# TouScruino-avr-ui1-v0.net
KiCad netlist of a schematic drawn in EAGLE
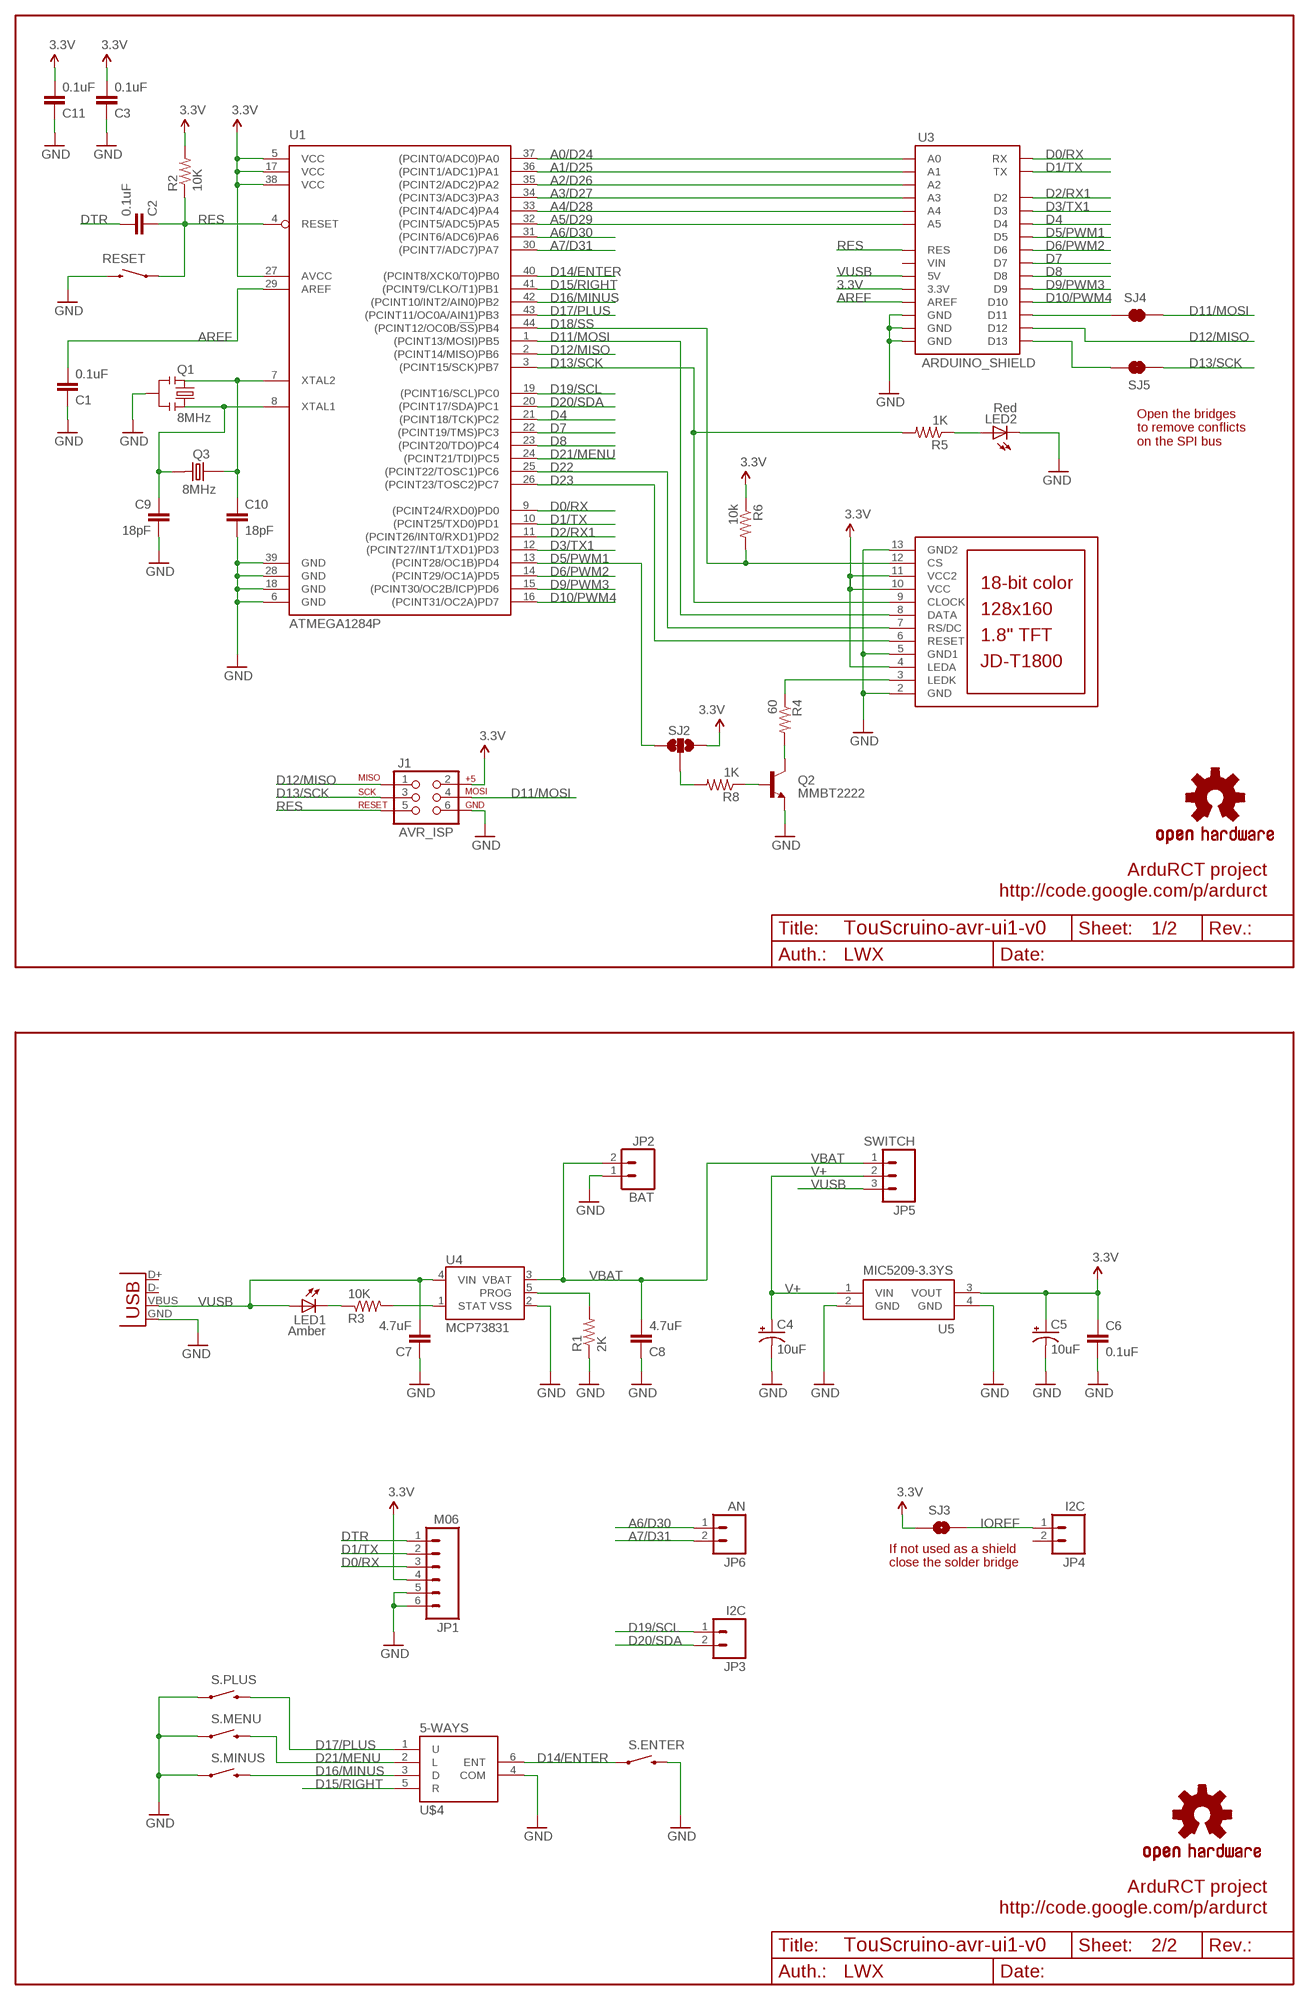
[diagram p0: schematic, sheet 1]

(export (version "E")
  (design (tool "Eeschema 10.0.6"))
  (components
    (comp (ref "C1")
      (value "0.1uF")
      (footprint "eagle-import:0805")
      (libsource (lib "eagle-import") (part "CAP0805"))
    )
    (comp (ref "C2")
      (value "0.1uF")
      (footprint "eagle-import:0805")
      (libsource (lib "eagle-import") (part "CAP0805"))
    )
    (comp (ref "C3")
      (value "0.1uF")
      (footprint "eagle-import:0805")
      (libsource (lib "eagle-import") (part "CAP0805"))
    )
    (comp (ref "C4")
      (value "10uF")
      (footprint "eagle-import:EIA3216")
      (libsource (lib "eagle-import") (part "CAP_POL1206"))
    )
    (comp (ref "C5")
      (value "10uF")
      (footprint "eagle-import:EIA3216")
      (libsource (lib "eagle-import") (part "CAP_POL1206"))
    )
    (comp (ref "C6")
      (value "0.1uF")
      (footprint "eagle-import:0805")
      (libsource (lib "eagle-import") (part "CAP0805"))
    )
    (comp (ref "C7")
      (value "4.7uF")
      (footprint "eagle-import:0805")
      (libsource (lib "eagle-import") (part "CAP0805"))
    )
    (comp (ref "C8")
      (value "4.7uF")
      (footprint "eagle-import:0805")
      (libsource (lib "eagle-import") (part "CAP0805"))
    )
    (comp (ref "C9")
      (value "18pF")
      (footprint "eagle-import:0603-CAP")
      (libsource (lib "eagle-import") (part "CAP0603-CAP"))
    )
    (comp (ref "C10")
      (value "18pF")
      (footprint "eagle-import:0603-CAP")
      (libsource (lib "eagle-import") (part "CAP0603-CAP"))
    )
    (comp (ref "C11")
      (value "0.1uF")
      (footprint "eagle-import:0805")
      (libsource (lib "eagle-import") (part "CAP0805"))
    )
    (comp (ref "J1")
      (value "AVR_ISP")
      (footprint "eagle-import:2X3")
      (libsource (lib "eagle-import") (part "AVR_SPI_PRG_6PTH"))
    )
    (comp (ref "JP1")
      (value "M06")
      (footprint "eagle-import:1X06")
      (libsource (lib "eagle-import") (part "M06"))
    )
    (comp (ref "JP2")
      (value "BAT")
      (footprint "eagle-import:JST-2-SMD")
      (libsource (lib "eagle-import") (part "M02-JST-2MM-SMT"))
    )
    (comp (ref "JP3")
      (value "I2C")
      (footprint "eagle-import:1X02")
      (libsource (lib "eagle-import") (part "M02"))
    )
    (comp (ref "JP4")
      (value "I2C")
      (footprint "eagle-import:1X02")
      (libsource (lib "eagle-import") (part "M02"))
    )
    (comp (ref "JP5")
      (value "SWITCH")
      (footprint "eagle-import:1X3_LONGPAD")
      (libsource (lib "eagle-import") (part "M03"))
    )
    (comp (ref "JP6")
      (value "AN")
      (footprint "eagle-import:1X02")
      (libsource (lib "eagle-import") (part "M02"))
    )
    (comp (ref "LCD1")
      (value "JD-T1800")
      (footprint "eagle-import:JD-T1800")
      (libsource (lib "eagle-import") (part "JD-T1800"))
    )
    (comp (ref "LED1")
      (value "Amber")
      (footprint "eagle-import:LED")
      (libsource (lib "eagle-import") (part "LED"))
    )
    (comp (ref "LED2")
      (value "Red")
      (footprint "eagle-import:LED")
      (libsource (lib "eagle-import") (part "LED"))
    )
    (comp (ref "Q1")
      (value "8MHz")
      (footprint "eagle-import:RESONATOR-SMD")
      (libsource (lib "eagle-import") (part "RESONATORSMD"))
    )
    (comp (ref "Q2")
      (value "MMBT2222")
      (footprint "eagle-import:SOT23-3")
      (libsource (lib "eagle-import") (part "TRANSISTOR_NPNSOT23-3"))
    )
    (comp (ref "Q3")
      (value "8MHz")
      (footprint "eagle-import:CRYSTAL_5X3.2")
      (libsource (lib "eagle-import") (part "CRYSTAL_5X3.2"))
    )
    (comp (ref "R1")
      (value "2K")
      (footprint "eagle-import:0805")
      (libsource (lib "eagle-import") (part "RESISTOR0805-RES"))
    )
    (comp (ref "R2")
      (value "10K")
      (footprint "eagle-import:0805")
      (libsource (lib "eagle-import") (part "RESISTOR0805-RES"))
    )
    (comp (ref "R3")
      (value "10K")
      (footprint "eagle-import:0805")
      (libsource (lib "eagle-import") (part "RESISTOR0805-RES"))
    )
    (comp (ref "R4")
      (value "60")
      (footprint "eagle-import:0805")
      (libsource (lib "eagle-import") (part "RESISTOR0805-RES"))
    )
    (comp (ref "R5")
      (value "1K")
      (footprint "eagle-import:0805")
      (libsource (lib "eagle-import") (part "RESISTOR0805-RES"))
    )
    (comp (ref "R6")
      (value "10k")
      (footprint "eagle-import:0805")
      (libsource (lib "eagle-import") (part "RESISTOR0805-RES"))
    )
    (comp (ref "R8")
      (value "1K")
      (footprint "eagle-import:0805")
      (libsource (lib "eagle-import") (part "RESISTOR0805-RES"))
    )
    (comp (ref "RESET")
      (value "SWITCH-MOMENTARY-2SMD")
      (footprint "eagle-import:TACTILE_SWITCH_SMD")
      (libsource (lib "eagle-import") (part "SWITCH-MOMENTARY-2SMD"))
    )
    (comp (ref "S.ENTER")
      (value "SWITCH_SMD")
      (footprint "eagle-import:TACTILE_SWITCH_SMD")
      (libsource (lib "eagle-import") (part "SWITCH_SMD"))
    )
    (comp (ref "S.MENU")
      (value "SWITCH_SMD")
      (footprint "eagle-import:TACTILE_SWITCH_SMD")
      (libsource (lib "eagle-import") (part "SWITCH_SMD"))
    )
    (comp (ref "S.MINUS")
      (value "SWITCH_SMD")
      (footprint "eagle-import:TACTILE_SWITCH_SMD")
      (libsource (lib "eagle-import") (part "SWITCH_SMD"))
    )
    (comp (ref "S.PLUS")
      (value "SWITCH_SMD")
      (footprint "eagle-import:TACTILE_SWITCH_SMD")
      (libsource (lib "eagle-import") (part "SWITCH_SMD"))
    )
    (comp (ref "SJ2")
      (value "SJ_2WAYS_1-2")
      (footprint "eagle-import:SJ_2WAYS_1-2_S")
      (libsource (lib "eagle-import") (part "SJ_2WAYS_1-2"))
    )
    (comp (ref "SJ3")
      (value "SOLDERJUMPERNO")
      (footprint "eagle-import:SJ_2S-NO")
      (libsource (lib "eagle-import") (part "SOLDERJUMPERNO"))
    )
    (comp (ref "SJ4")
      (value "SOLDERJUMPERTRACE")
      (footprint "eagle-import:SJ_2S-TRACE")
      (libsource (lib "eagle-import") (part "SOLDERJUMPERTRACE"))
    )
    (comp (ref "SJ5")
      (value "SOLDERJUMPERTRACE")
      (footprint "eagle-import:SJ_2S-TRACE")
      (libsource (lib "eagle-import") (part "SOLDERJUMPERTRACE"))
    )
    (comp (ref "U$3")
      (value "OSHW-LOGOM")
      (footprint "eagle-import:OSHW-LOGO-M")
      (libsource (lib "eagle-import") (part "OSHW-LOGOM"))
    )
    (comp (ref "U$4")
      (value "5-WAYS")
      (footprint "eagle-import:5-WAYS_ALPS")
      (libsource (lib "eagle-import") (part "5-WAYS"))
    )
    (comp (ref "U$5")
      (value "OSHW-LOGOM")
      (footprint "eagle-import:OSHW-LOGO-M")
      (libsource (lib "eagle-import") (part "OSHW-LOGOM"))
    )
    (comp (ref "U1")
      (value "ATMEGA1284P")
      (footprint "eagle-import:TQFP44")
      (libsource (lib "eagle-import") (part "ATMEGA324A"))
    )
    (comp (ref "U3")
      (value "ARDUINO_SHIELD")
      (footprint "eagle-import:ARDUINO_SHIELD")
      (libsource (lib "eagle-import") (part "ARDUINO_SHIELD"))
    )
    (comp (ref "U4")
      (value "MCP73831")
      (footprint "eagle-import:SOT23-5")
      (libsource (lib "eagle-import") (part "MCP73831"))
    )
    (comp (ref "U5")
      (value "MIC5209-3.3YS")
      (footprint "eagle-import:SOT223")
      (libsource (lib "eagle-import") (part "MIC5209"))
    )
    (comp (ref "X1")
      (value "USB")
      (footprint "eagle-import:USB-MICROB")
      (libsource (lib "eagle-import") (part "USB"))
    )
  )
  (nets
    (net (code "1") (name "/A0{slash}D24") (class "Default")
      (node (ref "U1") (pin "37") (pinfunction "(PCINT0/ADC0)PA0_37") (pintype "bidirectional"))
      (node (ref "U3") (pin "A0") (pinfunction "A0_A0") (pintype "bidirectional"))
    )
    (net (code "2") (name "/A1{slash}D25") (class "Default")
      (node (ref "U1") (pin "36") (pinfunction "(PCINT1/ADC1)PA1_36") (pintype "bidirectional"))
      (node (ref "U3") (pin "A1") (pinfunction "A1_A1") (pintype "bidirectional"))
    )
    (net (code "3") (name "/A2{slash}D26") (class "Default")
      (node (ref "U1") (pin "35") (pinfunction "(PCINT2/ADC2)PA2_35") (pintype "bidirectional"))
      (node (ref "U3") (pin "A2") (pinfunction "A2_A2") (pintype "bidirectional"))
    )
    (net (code "4") (name "/A3{slash}D27") (class "Default")
      (node (ref "U1") (pin "34") (pinfunction "(PCINT3/ADC3)PA3_34") (pintype "bidirectional"))
      (node (ref "U3") (pin "A3") (pinfunction "A3_A3") (pintype "bidirectional"))
    )
    (net (code "5") (name "/A4{slash}D28") (class "Default")
      (node (ref "U1") (pin "33") (pinfunction "(PCINT4/ADC4)PA4_33") (pintype "bidirectional"))
      (node (ref "U3") (pin "A4") (pinfunction "A4_A4") (pintype "bidirectional"))
    )
    (net (code "6") (name "/A5{slash}D29") (class "Default")
      (node (ref "U1") (pin "32") (pinfunction "(PCINT5/ADC5)PA5_32") (pintype "bidirectional"))
      (node (ref "U3") (pin "A5") (pinfunction "A5_A5") (pintype "bidirectional"))
    )
    (net (code "7") (name "/A6{slash}D30") (class "Default")
      (node (ref "JP6") (pin "1") (pinfunction "1_1") (pintype "passive"))
      (node (ref "U1") (pin "31") (pinfunction "(PCINT6/ADC6)PA6_31") (pintype "bidirectional"))
    )
    (net (code "8") (name "/A7{slash}D31") (class "Default")
      (node (ref "JP6") (pin "2") (pinfunction "2_2") (pintype "passive"))
      (node (ref "U1") (pin "30") (pinfunction "(PCINT7/ADC7)PA7_30") (pintype "bidirectional"))
    )
    (net (code "9") (name "/AREF") (class "Default")
      (node (ref "C1") (pin "2") (pinfunction "2_2") (pintype "passive"))
      (node (ref "U1") (pin "29") (pinfunction "AREF_29") (pintype "passive"))
      (node (ref "U3") (pin "AREF") (pinfunction "AREF_AREF") (pintype "bidirectional"))
    )
    (net (code "10") (name "/D0{slash}RX") (class "Default")
      (node (ref "JP1") (pin "3") (pinfunction "3_3") (pintype "passive"))
      (node (ref "U1") (pin "9") (pinfunction "(PCINT24/RXD0)PD0_9") (pintype "bidirectional"))
      (node (ref "U3") (pin "RX") (pinfunction "RX_RX") (pintype "bidirectional"))
    )
    (net (code "11") (name "/D1{slash}TX") (class "Default")
      (node (ref "JP1") (pin "2") (pinfunction "2_2") (pintype "passive"))
      (node (ref "U1") (pin "10") (pinfunction "(PCINT25/TXD0)PD1_10") (pintype "bidirectional"))
      (node (ref "U3") (pin "TX") (pinfunction "TX_TX") (pintype "bidirectional"))
    )
    (net (code "12") (name "/D2{slash}RX1") (class "Default")
      (node (ref "U1") (pin "11") (pinfunction "(PCINT26/INT0/RXD1)PD2_11") (pintype "bidirectional"))
      (node (ref "U3") (pin "D2") (pinfunction "D2_D2") (pintype "bidirectional"))
    )
    (net (code "13") (name "/D3{slash}TX1") (class "Default")
      (node (ref "U1") (pin "12") (pinfunction "(PCINT27/INT1/TXD1)PD3_12") (pintype "bidirectional"))
      (node (ref "U3") (pin "D3") (pinfunction "D3_D3") (pintype "bidirectional"))
    )
    (net (code "14") (name "/D4") (class "Default")
      (node (ref "U1") (pin "21") (pinfunction "(PCINT18/TCK)PC2_21") (pintype "output"))
      (node (ref "U3") (pin "D4") (pinfunction "D4_D4") (pintype "bidirectional"))
    )
    (net (code "15") (name "/D5{slash}PWM1") (class "Default")
      (node (ref "SJ2") (pin "1") (pinfunction "1_1") (pintype "passive"))
      (node (ref "U1") (pin "13") (pinfunction "(PCINT28/OC1B)PD4_13") (pintype "bidirectional"))
      (node (ref "U3") (pin "D5") (pinfunction "D5_D5") (pintype "bidirectional"))
    )
    (net (code "16") (name "/D6{slash}PWM2") (class "Default")
      (node (ref "U1") (pin "14") (pinfunction "(PCINT29/OC1A)PD5_14") (pintype "bidirectional"))
      (node (ref "U3") (pin "D6") (pinfunction "D6_D6") (pintype "bidirectional"))
    )
    (net (code "17") (name "/D7") (class "Default")
      (node (ref "U1") (pin "22") (pinfunction "(PCINT19/TMS)PC3_22") (pintype "output"))
      (node (ref "U3") (pin "D7") (pinfunction "D7_D7") (pintype "bidirectional"))
    )
    (net (code "18") (name "/D8") (class "Default")
      (node (ref "U1") (pin "23") (pinfunction "(PCINT20/TDO)PC4_23") (pintype "output"))
      (node (ref "U3") (pin "D8") (pinfunction "D8_D8") (pintype "bidirectional"))
    )
    (net (code "19") (name "/D9{slash}PWM3") (class "Default")
      (node (ref "U1") (pin "15") (pinfunction "(PCINT30/OC2B/ICP)PD6_15") (pintype "bidirectional"))
      (node (ref "U3") (pin "D9") (pinfunction "D9_D9") (pintype "bidirectional"))
    )
    (net (code "20") (name "/D10{slash}PWM4") (class "Default")
      (node (ref "U1") (pin "16") (pinfunction "(PCINT31/OC2A)PD7_16") (pintype "bidirectional"))
      (node (ref "U3") (pin "D10") (pinfunction "D10_D10") (pintype "bidirectional"))
    )
    (net (code "21") (name "/D11{slash}MOSI") (class "Default")
      (node (ref "J1") (pin "4") (pinfunction "4_4") (pintype "passive"))
      (node (ref "LCD1") (pin "8") (pinfunction "DATA_8") (pintype "bidirectional"))
      (node (ref "SJ4") (pin "2") (pinfunction "2_2") (pintype "passive"))
      (node (ref "U1") (pin "1") (pinfunction "(PCINT13/MOSI)PB5_1") (pintype "bidirectional"))
    )
    (net (code "22") (name "/D12{slash}MISO") (class "Default")
      (node (ref "J1") (pin "1") (pinfunction "1_1") (pintype "passive"))
      (node (ref "U1") (pin "2") (pinfunction "(PCINT14/MISO)PB6_2") (pintype "bidirectional"))
      (node (ref "U3") (pin "D12") (pinfunction "D12_D12") (pintype "bidirectional"))
    )
    (net (code "23") (name "/D13{slash}SCK") (class "Default")
      (node (ref "J1") (pin "3") (pinfunction "3_3") (pintype "passive"))
      (node (ref "LCD1") (pin "9") (pinfunction "CLOCK_9") (pintype "input"))
      (node (ref "R5") (pin "2") (pinfunction "2_2") (pintype "passive"))
      (node (ref "SJ5") (pin "1") (pinfunction "1_1") (pintype "passive"))
      (node (ref "U1") (pin "3") (pinfunction "(PCINT15/SCK)PB7_3") (pintype "bidirectional"))
    )
    (net (code "24") (name "/D14{slash}ENTER") (class "Default")
      (node (ref "S.ENTER") (pin "1") (pinfunction "1_1") (pintype "passive"))
      (node (ref "U$4") (pin "6") (pinfunction "ENT_6") (pintype "bidirectional"))
      (node (ref "U1") (pin "40") (pinfunction "(PCINT8/XCK0/T0)PB0_40") (pintype "bidirectional"))
    )
    (net (code "25") (name "/D15{slash}RIGHT") (class "Default")
      (node (ref "U$4") (pin "5") (pinfunction "R_5") (pintype "bidirectional"))
      (node (ref "U1") (pin "41") (pinfunction "(PCINT9/CLKO/T1)PB1_41") (pintype "bidirectional"))
    )
    (net (code "26") (name "/D16{slash}MINUS") (class "Default")
      (node (ref "S.MINUS") (pin "3") (pinfunction "2_3") (pintype "passive"))
      (node (ref "U$4") (pin "3") (pinfunction "D_3") (pintype "bidirectional"))
      (node (ref "U1") (pin "42") (pinfunction "(PCINT10/INT2/AIN0)PB2_42") (pintype "bidirectional"))
    )
    (net (code "27") (name "/D17{slash}PLUS") (class "Default")
      (node (ref "S.PLUS") (pin "3") (pinfunction "2_3") (pintype "passive"))
      (node (ref "U$4") (pin "1") (pinfunction "U_1") (pintype "bidirectional"))
      (node (ref "U1") (pin "43") (pinfunction "(PCINT11/OC0A/AIN1)PB3_43") (pintype "bidirectional"))
    )
    (net (code "28") (name "/D18{slash}SS") (class "Default")
      (node (ref "LCD1") (pin "12") (pinfunction "CS_12") (pintype "input"))
      (node (ref "R6") (pin "2") (pinfunction "2_2") (pintype "passive"))
      (node (ref "U1") (pin "44") (pinfunction "(PCINT12/OC0B/~{SS})PB4_44") (pintype "bidirectional"))
    )
    (net (code "29") (name "/D19{slash}SCL") (class "Default")
      (node (ref "JP3") (pin "1") (pinfunction "1_1") (pintype "passive"))
      (node (ref "U1") (pin "19") (pinfunction "(PCINT16/SCL)PC0_19") (pintype "output"))
    )
    (net (code "30") (name "/D20{slash}SDA") (class "Default")
      (node (ref "JP3") (pin "2") (pinfunction "2_2") (pintype "passive"))
      (node (ref "U1") (pin "20") (pinfunction "(PCINT17/SDA)PC1_20") (pintype "output"))
    )
    (net (code "31") (name "/D21{slash}MENU") (class "Default")
      (node (ref "S.MENU") (pin "3") (pinfunction "2_3") (pintype "passive"))
      (node (ref "U$4") (pin "2") (pinfunction "L_2") (pintype "bidirectional"))
      (node (ref "U1") (pin "24") (pinfunction "(PCINT21/TDI)PC5_24") (pintype "output"))
    )
    (net (code "32") (name "/D22") (class "Default")
      (node (ref "LCD1") (pin "7") (pinfunction "RS/DC_7") (pintype "input"))
      (node (ref "U1") (pin "25") (pinfunction "(PCINT22/TOSC1)PC6_25") (pintype "output"))
    )
    (net (code "33") (name "/D23") (class "Default")
      (node (ref "LCD1") (pin "6") (pinfunction "RESET_6") (pintype "input"))
      (node (ref "U1") (pin "26") (pinfunction "(PCINT23/TOSC2)PC7_26") (pintype "output"))
    )
    (net (code "34") (name "/DTR") (class "Default")
      (node (ref "C2") (pin "2") (pinfunction "2_2") (pintype "passive"))
      (node (ref "JP1") (pin "1") (pinfunction "1_1") (pintype "passive"))
    )
    (net (code "35") (name "/IOREF") (class "Default")
      (node (ref "JP4") (pin "1") (pinfunction "1_1") (pintype "passive"))
      (node (ref "SJ3") (pin "2") (pinfunction "2_2") (pintype "passive"))
    )
    (net (code "36") (name "/RES") (class "Default")
      (node (ref "C2") (pin "1") (pinfunction "1_1") (pintype "passive"))
      (node (ref "J1") (pin "5") (pinfunction "5_5") (pintype "passive"))
      (node (ref "R2") (pin "1") (pinfunction "1_1") (pintype "passive"))
      (node (ref "RESET") (pin "1") (pinfunction "1_1") (pintype "passive"))
      (node (ref "U1") (pin "4") (pinfunction "RESET_4") (pintype "input"))
      (node (ref "U3") (pin "RES") (pinfunction "RES_RES") (pintype "bidirectional"))
    )
    (net (code "37") (name "/V+") (class "Default")
      (node (ref "C4") (pin "A") (pinfunction "+_A") (pintype "passive"))
      (node (ref "JP5") (pin "2") (pinfunction "2_2") (pintype "passive"))
      (node (ref "U5") (pin "1") (pinfunction "VIN_1") (pintype "bidirectional"))
    )
    (net (code "38") (name "/VBAT") (class "Default")
      (node (ref "C8") (pin "2") (pinfunction "2_2") (pintype "passive"))
      (node (ref "JP2") (pin "2") (pinfunction "2_2") (pintype "passive"))
      (node (ref "JP5") (pin "1") (pinfunction "1_1") (pintype "passive"))
      (node (ref "U4") (pin "3") (pinfunction "VBAT_3") (pintype "power_in"))
    )
    (net (code "39") (name "/VUSB") (class "Default")
      (node (ref "C7") (pin "2") (pinfunction "2_2") (pintype "passive"))
      (node (ref "JP5") (pin "3") (pinfunction "3_3") (pintype "passive"))
      (node (ref "LED1") (pin "A1") (pinfunction "A_A1") (pintype "passive"))
      (node (ref "U3") (pin "5V") (pinfunction "5V_5V") (pintype "bidirectional"))
      (node (ref "U4") (pin "4") (pinfunction "VIN_4") (pintype "power_in"))
      (node (ref "X1") (pin "VBUS") (pinfunction "VBUS_VBUS") (pintype "bidirectional"))
    )
    (net (code "40") (name "3.3V") (class "Default")
      (node (ref "C11") (pin "2") (pinfunction "2_2") (pintype "passive"))
      (node (ref "C3") (pin "2") (pinfunction "2_2") (pintype "passive"))
      (node (ref "C5") (pin "A") (pinfunction "+_A") (pintype "passive"))
      (node (ref "C6") (pin "1") (pinfunction "1_1") (pintype "passive"))
      (node (ref "J1") (pin "2") (pinfunction "2_2") (pintype "passive"))
      (node (ref "JP1") (pin "4") (pinfunction "4_4") (pintype "passive"))
      (node (ref "LCD1") (pin "10") (pinfunction "VCC_10") (pintype "power_in"))
      (node (ref "LCD1") (pin "11") (pinfunction "VCC2_11") (pintype "power_in"))
      (node (ref "LCD1") (pin "4") (pinfunction "LEDA_4") (pintype "input"))
      (node (ref "R2") (pin "2") (pinfunction "2_2") (pintype "passive"))
      (node (ref "R6") (pin "1") (pinfunction "1_1") (pintype "passive"))
      (node (ref "SJ2") (pin "3") (pinfunction "3_3") (pintype "passive"))
      (node (ref "SJ3") (pin "1") (pinfunction "1_1") (pintype "passive"))
      (node (ref "U1") (pin "17") (pinfunction "VCC_17") (pintype "power_in"))
      (node (ref "U1") (pin "27") (pinfunction "AVCC_27") (pintype "power_in"))
      (node (ref "U1") (pin "38") (pinfunction "VCC_38") (pintype "power_in"))
      (node (ref "U1") (pin "5") (pinfunction "VCC_5") (pintype "power_in"))
      (node (ref "U3") (pin "3.3V") (pinfunction "3.3V_3.3V") (pintype "bidirectional"))
      (node (ref "U5") (pin "3") (pinfunction "VOUT_3") (pintype "bidirectional"))
    )
    (net (code "41") (name "GND") (class "Default")
      (node (ref "C1") (pin "1") (pinfunction "1_1") (pintype "passive"))
      (node (ref "C10") (pin "2") (pinfunction "2_2") (pintype "passive"))
      (node (ref "C11") (pin "1") (pinfunction "1_1") (pintype "passive"))
      (node (ref "C3") (pin "1") (pinfunction "1_1") (pintype "passive"))
      (node (ref "C4") (pin "C") (pinfunction "-_C") (pintype "passive"))
      (node (ref "C5") (pin "C") (pinfunction "-_C") (pintype "passive"))
      (node (ref "C6") (pin "2") (pinfunction "2_2") (pintype "passive"))
      (node (ref "C7") (pin "1") (pinfunction "1_1") (pintype "passive"))
      (node (ref "C8") (pin "1") (pinfunction "1_1") (pintype "passive"))
      (node (ref "C9") (pin "2") (pinfunction "2_2") (pintype "passive"))
      (node (ref "J1") (pin "6") (pinfunction "6_6") (pintype "passive"))
      (node (ref "JP1") (pin "5") (pinfunction "5_5") (pintype "passive"))
      (node (ref "JP1") (pin "6") (pinfunction "6_6") (pintype "passive"))
      (node (ref "JP2") (pin "1") (pinfunction "1_1") (pintype "passive"))
      (node (ref "LCD1") (pin "13") (pinfunction "GND2_13") (pintype "power_in"))
      (node (ref "LCD1") (pin "2") (pinfunction "GND_2") (pintype "power_in"))
      (node (ref "LCD1") (pin "5") (pinfunction "GND1_5") (pintype "power_in"))
      (node (ref "LED2") (pin "C1") (pinfunction "C_C1") (pintype "passive"))
      (node (ref "Q1") (pin "2") (pinfunction "2_2") (pintype "passive"))
      (node (ref "Q2") (pin "2") (pinfunction "E_2") (pintype "passive"))
      (node (ref "R1") (pin "1") (pinfunction "1_1") (pintype "passive"))
      (node (ref "RESET") (pin "3") (pinfunction "2_3") (pintype "passive"))
      (node (ref "S.ENTER") (pin "3") (pinfunction "2_3") (pintype "passive"))
      (node (ref "S.MENU") (pin "1") (pinfunction "1_1") (pintype "passive"))
      (node (ref "S.MINUS") (pin "1") (pinfunction "1_1") (pintype "passive"))
      (node (ref "S.PLUS") (pin "1") (pinfunction "1_1") (pintype "passive"))
      (node (ref "U$4") (pin "4") (pinfunction "COM_4") (pintype "bidirectional"))
      (node (ref "U1") (pin "18") (pinfunction "GND_18") (pintype "power_in"))
      (node (ref "U1") (pin "28") (pinfunction "GND_28") (pintype "power_in"))
      (node (ref "U1") (pin "39") (pinfunction "GND_39") (pintype "power_in"))
      (node (ref "U1") (pin "6") (pinfunction "GND_6") (pintype "power_in"))
      (node (ref "U3") (pin "GND@0") (pinfunction "GND_GND@0") (pintype "bidirectional"))
      (node (ref "U3") (pin "GND@1") (pinfunction "GND_GND@1") (pintype "bidirectional"))
      (node (ref "U3") (pin "GND@2") (pinfunction "GND_GND@2") (pintype "bidirectional"))
      (node (ref "U4") (pin "2") (pinfunction "VSS_2") (pintype "power_in"))
      (node (ref "U5") (pin "2") (pinfunction "GND_2") (pintype "bidirectional"))
      (node (ref "U5") (pin "4") (pinfunction "GND_4") (pintype "bidirectional"))
      (node (ref "X1") (pin "GND") (pinfunction "GND_GND") (pintype "bidirectional"))
    )
    (net (code "42") (name "Net-(LCD1-LEDK)") (class "Default")
      (node (ref "LCD1") (pin "3") (pinfunction "LEDK_3") (pintype "input"))
      (node (ref "R4") (pin "1") (pinfunction "1_1") (pintype "passive"))
    )
    (net (code "43") (name "Net-(LED1-C)") (class "Default")
      (node (ref "LED1") (pin "C1") (pinfunction "C_C1") (pintype "passive"))
      (node (ref "R3") (pin "1") (pinfunction "1_1") (pintype "passive"))
    )
    (net (code "44") (name "Net-(LED2-A)") (class "Default")
      (node (ref "LED2") (pin "A1") (pinfunction "A_A1") (pintype "passive"))
      (node (ref "R5") (pin "1") (pinfunction "1_1") (pintype "passive"))
    )
    (net (code "45") (name "Net-(Q2-B)") (class "Default")
      (node (ref "Q2") (pin "1") (pinfunction "B_1") (pintype "passive"))
      (node (ref "R8") (pin "1") (pinfunction "1_1") (pintype "passive"))
    )
    (net (code "46") (name "Net-(Q2-C)") (class "Default")
      (node (ref "Q2") (pin "3") (pinfunction "C_3") (pintype "passive"))
      (node (ref "R4") (pin "2") (pinfunction "2_2") (pintype "passive"))
    )
    (net (code "47") (name "Net-(R8-Pad2)") (class "Default")
      (node (ref "R8") (pin "2") (pinfunction "2_2") (pintype "passive"))
      (node (ref "SJ2") (pin "2") (pinfunction "2_2") (pintype "passive"))
    )
    (net (code "48") (name "Net-(SJ4-Pad1)") (class "Default")
      (node (ref "SJ4") (pin "1") (pinfunction "1_1") (pintype "passive"))
      (node (ref "U3") (pin "D11") (pinfunction "D11_D11") (pintype "bidirectional"))
    )
    (net (code "49") (name "Net-(SJ5-Pad2)") (class "Default")
      (node (ref "SJ5") (pin "2") (pinfunction "2_2") (pintype "passive"))
      (node (ref "U3") (pin "D13") (pinfunction "D13_D13") (pintype "bidirectional"))
    )
    (net (code "50") (name "Net-(U1-XTAL1)") (class "Default")
      (node (ref "C9") (pin "1") (pinfunction "1_1") (pintype "passive"))
      (node (ref "Q1") (pin "1") (pinfunction "1_1") (pintype "passive"))
      (node (ref "Q3") (pin "2") (pinfunction "2_2") (pintype "passive"))
      (node (ref "U1") (pin "8") (pinfunction "XTAL1_8") (pintype "bidirectional"))
    )
    (net (code "51") (name "Net-(U1-XTAL2)") (class "Default")
      (node (ref "C10") (pin "1") (pinfunction "1_1") (pintype "passive"))
      (node (ref "Q1") (pin "3") (pinfunction "3_3") (pintype "passive"))
      (node (ref "Q3") (pin "1") (pinfunction "1_1") (pintype "passive"))
      (node (ref "U1") (pin "7") (pinfunction "XTAL2_7") (pintype "bidirectional"))
    )
    (net (code "52") (name "Net-(U4-PROG)") (class "Default")
      (node (ref "R1") (pin "2") (pinfunction "2_2") (pintype "passive"))
      (node (ref "U4") (pin "5") (pinfunction "PROG_5") (pintype "input"))
    )
    (net (code "53") (name "Net-(U4-STAT)") (class "Default")
      (node (ref "R3") (pin "2") (pinfunction "2_2") (pintype "passive"))
      (node (ref "U4") (pin "1") (pinfunction "STAT_1") (pintype "output"))
    )
    (net (code "54") (name "unconnected-(JP4-Pad2)") (class "Default")
      (node (ref "JP4") (pin "2") (pinfunction "2_2") (pintype "passive"))
    )
    (net (code "55") (name "unconnected-(U3-PadVIN)") (class "Default")
      (node (ref "U3") (pin "VIN") (pinfunction "VIN_VIN") (pintype "bidirectional"))
    )
    (net (code "56") (name "unconnected-(X1-PadD+)") (class "Default")
      (node (ref "X1") (pin "D+") (pinfunction "D+_D+") (pintype "bidirectional"))
    )
    (net (code "57") (name "unconnected-(X1-PadD-)") (class "Default")
      (node (ref "X1") (pin "D-") (pinfunction "D-_D-") (pintype "bidirectional"))
    )
  )
)
